# Power-Sheet-1.net
KiCad netlist of a schematic drawn in Altium Designer
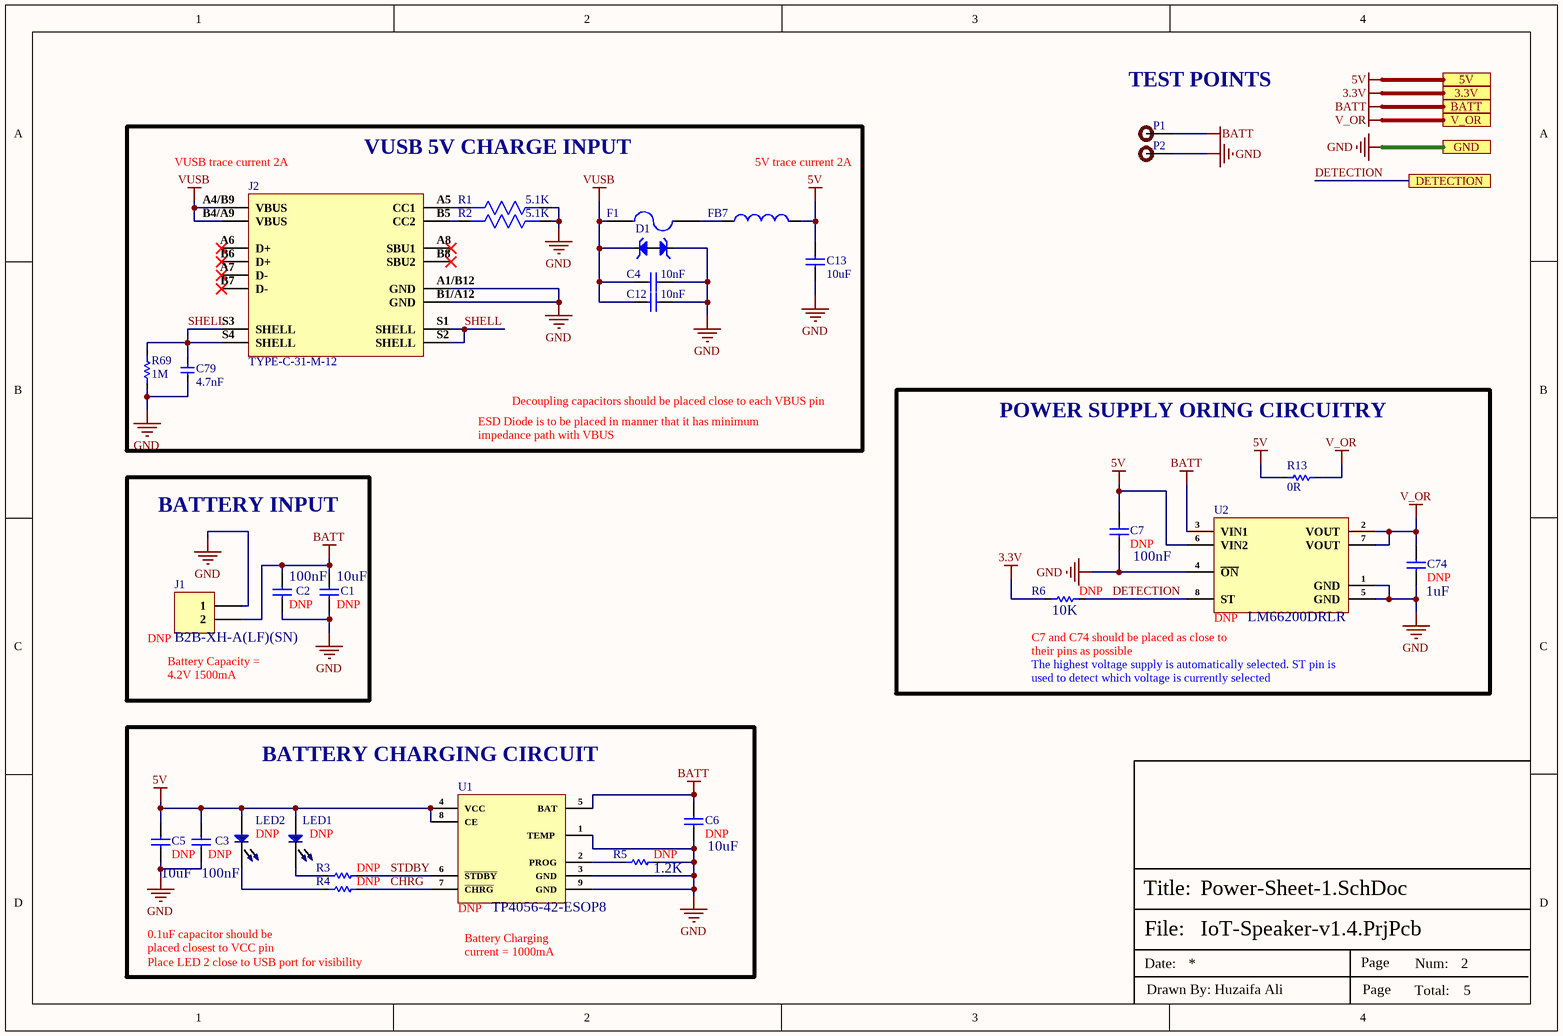
[diagram p0: Power-Sheet-1.SchDoc]

(export (version "E")
  (design (tool "Eeschema 10.0.6"))
  (components
    (comp (ref "C1")
      (value "DNP")
      (footprint "Cap-0805")
      (description "CAP CER 10UF 25V X5R 0805")
      (fields
        (field (name "MANUFACTURER") "Yageo")
        (field (name "MANUFACTURER PART NUMBER") "CC0805KKX5R8BB106")
      )
      (libsource (lib "eSpark_centralized_Library(2022)") (part "CC0805KKX5R8BB106"))
    )
    (comp (ref "C2")
      (value "DNP")
      (footprint "Cap-0402")
      (description "CAP CER 0.1UF 25V X5R 0402")
      (fields
        (field (name "MANUFACTURER") "Yageo")
        (field (name "MANUFACTURER PART NUMBER") "CC0402KRX5R8BB104")
      )
      (libsource (lib "eSpark_centralized_Library(2022)") (part "CC0402KRX5R8BB104"))
    )
    (comp (ref "C3")
      (value "DNP")
      (footprint "Cap-0402")
      (description "CAP CER 0.1UF 25V X5R 0402")
      (fields
        (field (name "MANUFACTURER") "Yageo")
        (field (name "MANUFACTURER PART NUMBER") "CC0402KRX5R8BB104")
      )
      (libsource (lib "eSpark_centralized_Library(2022)") (part "CC0402KRX5R8BB104"))
    )
    (comp (ref "C4")
      (value "10nF")
      (footprint "Cap-0603")
      (description "CAP CER 10000PF 50V C0G/NPO 0603")
      (fields
        (field (name "MANUFACTURER") "Yageo")
        (field (name "MANUFACTURER PART NUMBER") "CC0603JRNPO9BN103")
      )
      (libsource (lib "eSpark_centralized_Library(2022)") (part "CC0603JRNPO9BN103"))
    )
    (comp (ref "C5")
      (value "DNP")
      (footprint "Cap-0805")
      (description "CAP CER 10UF 25V X5R 0805")
      (fields
        (field (name "MANUFACTURER") "Yageo")
        (field (name "MANUFACTURER PART NUMBER") "CC0805KKX5R8BB106")
      )
      (libsource (lib "eSpark_centralized_Library(2022)") (part "CC0805KKX5R8BB106"))
    )
    (comp (ref "C6")
      (value "DNP")
      (footprint "Cap-0805")
      (description "CAP CER 10UF 25V X5R 0805")
      (fields
        (field (name "MANUFACTURER") "Yageo")
        (field (name "MANUFACTURER PART NUMBER") "CC0805KKX5R8BB106")
      )
      (libsource (lib "eSpark_centralized_Library(2022)") (part "CC0805KKX5R8BB106"))
    )
    (comp (ref "C7")
      (value "DNP")
      (footprint "Cap-0402")
      (description "CAP CER 0.1UF 25V X5R 0402")
      (fields
        (field (name "MANUFACTURER") "Yageo")
        (field (name "MANUFACTURER PART NUMBER") "CC0402KRX5R8BB104")
      )
      (libsource (lib "eSpark_centralized_Library(2022)") (part "CC0402KRX5R8BB104"))
    )
    (comp (ref "C12")
      (value "10nF")
      (footprint "Cap-0603")
      (description "CAP CER 10000PF 50V C0G/NPO 0603")
      (fields
        (field (name "MANUFACTURER") "Yageo")
        (field (name "MANUFACTURER PART NUMBER") "CC0603JRNPO9BN103")
      )
      (libsource (lib "eSpark_centralized_Library(2022)") (part "CC0603JRNPO9BN103"))
    )
    (comp (ref "C13")
      (value "10uF")
      (footprint "Cap-0805")
      (description "CAP CER 10UF 25V X5R 0805")
      (fields
        (field (name "MANUFACTURER") "Yageo")
        (field (name "MANUFACTURER PART NUMBER") "CC0805KKX5R8BB106")
      )
      (libsource (lib "eSpark_centralized_Library(2022)") (part "CC0805KKX5R8BB106"))
    )
    (comp (ref "C74")
      (value "DNP")
      (footprint "Cap-0603")
      (description "CAP CER 1UF 25V X5R 0603")
      (fields
        (field (name "MANUFACTURER") "Yageo")
        (field (name "MANUFACTURER PART NUMBER") "CC0603KRX5R8BB105")
      )
      (libsource (lib "eSpark_centralized_Library(2022)") (part "CC0603KRX5R8BB105"))
    )
    (comp (ref "C79")
      (value "4.7nF")
      (footprint "Cap-1206")
      (description "CAP CER 4700PF 1KV X7R 1206")
      (fields
        (field (name "MANUFACTURER") "Yageo")
        (field (name "MANUFACTURER PART NUMBER") "CC1206KKX7RCBB472")
      )
      (libsource (lib "eSpark Libraries") (part "CC1206KKX7RCBB472"))
    )
    (comp (ref "D1")
      (value "PESD5V0H1BSFYL")
      (footprint "DSN0603-2")
      (description "TVS DIODE 5VWM 6.3VC DSN0603-2")
      (fields (field (name "MANUFACTURER") "Nexperia") (field (name "LCSC PART NUMBER") "C477989"))
      (libsource (lib "eSpark Libraries") (part "PESD5V0H1BSFYL"))
    )
    (comp (ref "F1")
      (value "BSMD0805L-200")
      (footprint "Fuse-0805")
      (description "6V 2A 50A 1W -40℃~+85℃ 4A 4mΩ 5s 45mΩ 0805 Resettable Fuses ROHS")
      (fields (field (name "MANUFACTURER") "BHFUSE") (field (name "LCSC PART NUMBER") "C2757931"))
      (libsource (lib "eSpark_centralized_Library(2022)") (part "BSMD0805L-200"))
    )
    (comp (ref "FB7")
      (value "100MHz")
      (footprint "IND-1206")
      (description "FERRITE BEAD 120 OHM 1206 1LN")
      (fields
        (field (name "MANUFACTURER") "Murata")
        (field (name "MANUFACTURER PART NUMBER") "BLM31PG121SN1L")
      )
      (libsource (lib "eSpark_centralized_Library(2022)") (part "BLM31PG121SN1L"))
    )
    (comp (ref "J1")
      (value "DNP")
      (footprint "B2B-XH-A(LF)(SN)_")
      (description "Conn Shrouded Header (4 Sides) HDR 2 POS 2.5mm Solder ST Thru-Hole Box")
      (fields
        (field (name "MANUFACTURER") "JST")
        (field (name "MANUFACTURER PART NUMBER") "B2B-XH-A(LF)(SN)")
      )
      (libsource (lib "eSpark_centralized_Library(2022)") (part "B2B-XH-A(LF)(SN)"))
    )
    (comp (ref "J2")
      (value "TYPE-C-31-M-12")
      (footprint "TYPE-C-31-M-12_")
      (description "250mA 1 16 Female Type-C SMD USB Connectors ROHS")
      (fields
        (field (name "MANUFACTURER") "Korean Hroparts Elec")
        (field (name "LCSC PART NUMBER") "C165948")
      )
      (libsource (lib "eSpark_centralized_Library(2022)") (part "TYPE-C-31-M-12"))
    )
    (comp (ref "LED1")
      (value "DNP")
      (footprint "LED-0603")
      (description "Emerald 0603 Light Emitting Diodes (LED) ROHS")
      (fields
        (field (name "MANUFACTURER") "Foshan NationStar Optoelectronics")
        (field (name "MANUFACTURER PART NUMBER") "NCD0603G2")
      )
      (libsource (lib "eSpark_centralized_Library(2022)") (part "NCD0603G2"))
    )
    (comp (ref "LED2")
      (value "DNP")
      (footprint "LED-0603")
      (description "0603 Light Emitting Diodes (LED) ROHS")
      (fields
        (field (name "MANUFACTURER") "Foshan NationStar Optoelectronics")
        (field (name "MANUFACTURER PART NUMBER") "NCD0603R3")
      )
      (libsource (lib "eSpark_centralized_Library(2022)") (part "NCD0603R3"))
    )
    (comp (ref "P1")
      (value "TEST POINT")
      (footprint "Test-point")
      (description "Test Point ON")
      (libsource (lib "eSpark_centralized_Library(2022)") (part "TEST POINT"))
    )
    (comp (ref "P2")
      (value "TEST POINT")
      (footprint "Test-point")
      (description "Test Point ON")
      (libsource (lib "eSpark_centralized_Library(2022)") (part "TEST POINT"))
    )
    (comp (ref "R1")
      (value "5.1K")
      (footprint "Res-0603")
      (description "RES 5.1K OHM 1% 1/10W 0603")
      (fields
        (field (name "MANUFACTURER") "Yageo")
        (field (name "MANUFACTURER PART NUMBER") "RC0603FR-075K1L")
      )
      (libsource (lib "eSpark_centralized_Library(2022)") (part "RC0603FR-075K1L"))
    )
    (comp (ref "R2")
      (value "5.1K")
      (footprint "Res-0603")
      (description "RES 5.1K OHM 1% 1/10W 0603")
      (fields
        (field (name "MANUFACTURER") "Yageo")
        (field (name "MANUFACTURER PART NUMBER") "RC0603FR-075K1L")
      )
      (libsource (lib "eSpark_centralized_Library(2022)") (part "RC0603FR-075K1L"))
    )
    (comp (ref "R3")
      (value "DNP")
      (footprint "Res-0603")
      (description "RES SMD 220 OHM 1% 1/10W 0603")
      (fields
        (field (name "MANUFACTURER") "Yageo")
        (field (name "MANUFACTURER PART NUMBER") "RC0603FR-07220RL")
      )
      (libsource (lib "eSpark_centralized_Library(2022)") (part "RC0603FR-07220RL"))
    )
    (comp (ref "R4")
      (value "DNP")
      (footprint "Res-0603")
      (description "RES  SMD 330R 100 mW 0603")
      (fields
        (field (name "MANUFACTURER") "Yageo")
        (field (name "MANUFACTURER PART NUMBER") "RC0603JR-07330RL")
      )
      (libsource (lib "eSpark_centralized_Library(2022)") (part "RC0603JR-07330RL"))
    )
    (comp (ref "R5")
      (value "DNP")
      (footprint "Res-0603")
      (description "Thick Film Resistors 75V 1.2kΩ 0603 Chip Resistor - Surface Mount ROHS")
      (fields
        (field (name "MANUFACTURER") "UNI-ROYAL")
        (field (name "MANUFACTURER PART NUMBER") "0603WAF1201T5E")
      )
      (libsource (lib "eSpark_centralized_Library(2022)") (part "0603WAF1201T5E"))
    )
    (comp (ref "R6")
      (value "DNP")
      (footprint "Res-0603")
      (description "RES SMD 10K Ohm 1% 1/10W 0603")
      (fields
        (field (name "MANUFACTURER") "Yageo")
        (field (name "MANUFACTURER PART NUMBER") "RC0603FR-0710KL")
      )
      (libsource (lib "eSpark_centralized_Library(2022)") (part "RC0603FR-0710KL"))
    )
    (comp (ref "R13")
      (value "0R")
      (footprint "Res-0603")
      (description "RES 0 OHM JUMPER 1/10W 0603")
      (fields
        (field (name "MANUFACTURER") "Yageo")
        (field (name "MANUFACTURER PART NUMBER") "RC0603JR-070RL")
      )
      (libsource (lib "eSpark Libraries") (part "RC0603JR-070RL"))
    )
    (comp (ref "R69")
      (value "1M")
      (footprint "Res-0603")
      (description "RES SMD 1M OHM 1% 1/10W 0603")
      (fields
        (field (name "MANUFACTURER") "Yageo")
        (field (name "MANUFACTURER PART NUMBER") "RC0603FR-071ML")
      )
      (libsource (lib "eSpark Libraries") (part "RC0603FR-071ML"))
    )
    (comp (ref "U1")
      (value "DNP")
      (footprint "ESOP-8")
      (description "ESOP-8 Battery Management ICs ROHS")
      (fields
        (field (name "MANUFACTURER") "TOPPOWER")
        (field (name "MANUFACTURER PART NUMBER") "TP4056-42-ESOP8")
      )
      (libsource (lib "eSpark_centralized_Library(2022)") (part "TP4056-42-ESOP8"))
    )
    (comp (ref "U2")
      (value "DNP")
      (footprint "SOT-583")
      (description "OR Controller N+1 ORing Controller N-Channel 2:1 SOT-583")
      (fields
        (field (name "MANUFACTURER") "Texas Instruments")
        (field (name "MANUFACTURER PART NUMBER") "LM66200DRLR")
      )
      (libsource (lib "eSpark_centralized_Library(2022)") (part "LM66200DRLR"))
    )
  )
  (nets
    (net (code "1") (name "/CHRG") (class "Default")
      (node (ref "R4") (pin "2") (pinfunction "2_2") (pintype "passive"))
      (node (ref "U1") (pin "7") (pinfunction "~{CHRG}_7") (pintype "passive"))
    )
    (net (code "2") (name "/DETECTION") (class "Default")
      (node (ref "R6") (pin "2") (pinfunction "2_2") (pintype "passive"))
      (node (ref "U2") (pin "8") (pinfunction "ST_8") (pintype "passive"))
    )
    (net (code "3") (name "/SHELL") (class "Default")
      (node (ref "C79") (pin "2") (pinfunction "2_2") (pintype "passive"))
      (node (ref "J2") (pin "S1") (pinfunction "SHELL_S1") (pintype "passive"))
      (node (ref "J2") (pin "S2") (pinfunction "SHELL_S2") (pintype "passive"))
      (node (ref "J2") (pin "S3") (pinfunction "SHELL_S3") (pintype "passive"))
      (node (ref "J2") (pin "S4") (pinfunction "SHELL_S4") (pintype "passive"))
      (node (ref "R69") (pin "2") (pinfunction "2_2") (pintype "passive"))
    )
    (net (code "4") (name "/STDBY") (class "Default")
      (node (ref "R3") (pin "2") (pinfunction "2_2") (pintype "passive"))
      (node (ref "U1") (pin "6") (pinfunction "~{STDBY}_6") (pintype "passive"))
    )
    (net (code "5") (name "3.3V") (class "Default")
      (node (ref "R6") (pin "1") (pinfunction "1_1") (pintype "passive"))
    )
    (net (code "6") (name "5V") (class "Default")
      (node (ref "C13") (pin "2") (pinfunction "2_2") (pintype "passive"))
      (node (ref "C3") (pin "2") (pinfunction "2_2") (pintype "passive"))
      (node (ref "C5") (pin "2") (pinfunction "2_2") (pintype "passive"))
      (node (ref "C7") (pin "2") (pinfunction "2_2") (pintype "passive"))
      (node (ref "FB7") (pin "2") (pinfunction "2_2") (pintype "passive"))
      (node (ref "LED1") (pin "1") (pinfunction "1_1") (pintype "passive"))
      (node (ref "LED2") (pin "1") (pinfunction "1_1") (pintype "passive"))
      (node (ref "R13") (pin "1") (pinfunction "1_1") (pintype "passive"))
      (node (ref "U1") (pin "4") (pinfunction "VCC_4") (pintype "passive"))
      (node (ref "U1") (pin "8") (pinfunction "CE_8") (pintype "passive"))
      (node (ref "U2") (pin "6") (pinfunction "VIN2_6") (pintype "passive"))
    )
    (net (code "7") (name "BATT") (class "Default")
      (node (ref "C1") (pin "2") (pinfunction "2_2") (pintype "passive"))
      (node (ref "C2") (pin "2") (pinfunction "2_2") (pintype "passive"))
      (node (ref "C6") (pin "2") (pinfunction "2_2") (pintype "passive"))
      (node (ref "J1") (pin "2") (pinfunction "2_2") (pintype "passive"))
      (node (ref "P1") (pin "1") (pinfunction "1_1") (pintype "passive"))
      (node (ref "U1") (pin "5") (pinfunction "BAT_5") (pintype "passive"))
      (node (ref "U2") (pin "3") (pinfunction "VIN1_3") (pintype "passive"))
    )
    (net (code "8") (name "GND") (class "Default")
      (node (ref "C1") (pin "1") (pinfunction "1_1") (pintype "passive"))
      (node (ref "C12") (pin "2") (pinfunction "2_2") (pintype "passive"))
      (node (ref "C13") (pin "1") (pinfunction "1_1") (pintype "passive"))
      (node (ref "C2") (pin "1") (pinfunction "1_1") (pintype "passive"))
      (node (ref "C3") (pin "1") (pinfunction "1_1") (pintype "passive"))
      (node (ref "C4") (pin "2") (pinfunction "2_2") (pintype "passive"))
      (node (ref "C5") (pin "1") (pinfunction "1_1") (pintype "passive"))
      (node (ref "C6") (pin "1") (pinfunction "1_1") (pintype "passive"))
      (node (ref "C7") (pin "1") (pinfunction "1_1") (pintype "passive"))
      (node (ref "C74") (pin "1") (pinfunction "1_1") (pintype "passive"))
      (node (ref "C79") (pin "1") (pinfunction "1_1") (pintype "passive"))
      (node (ref "D1") (pin "2") (pinfunction "2_2") (pintype "passive"))
      (node (ref "J1") (pin "1") (pinfunction "1_1") (pintype "passive"))
      (node (ref "J2") (pin "A1/B12") (pinfunction "GND_A1/B12") (pintype "power_in"))
      (node (ref "J2") (pin "B1/A12") (pinfunction "GND_B1/A12") (pintype "power_in"))
      (node (ref "P2") (pin "1") (pinfunction "1_1") (pintype "passive"))
      (node (ref "R1") (pin "1") (pintype "passive"))
      (node (ref "R2") (pin "1") (pintype "passive"))
      (node (ref "R5") (pin "1") (pinfunction "1_1") (pintype "passive"))
      (node (ref "R69") (pin "1") (pinfunction "1_1") (pintype "passive"))
      (node (ref "U1") (pin "1") (pinfunction "TEMP_1") (pintype "passive"))
      (node (ref "U1") (pin "3") (pinfunction "GND_3") (pintype "passive"))
      (node (ref "U1") (pin "9") (pinfunction "GND_9") (pintype "passive"))
      (node (ref "U2") (pin "1") (pinfunction "GND_1") (pintype "passive"))
      (node (ref "U2") (pin "4") (pinfunction "~{ON}_4") (pintype "passive"))
      (node (ref "U2") (pin "5") (pinfunction "GND_5") (pintype "passive"))
    )
    (net (code "9") (name "Net-(F1-Pad2)") (class "Default")
      (node (ref "F1") (pin "2") (pinfunction "2_2") (pintype "passive"))
      (node (ref "FB7") (pin "1") (pinfunction "1_1") (pintype "passive"))
    )
    (net (code "10") (name "Net-(J2-CC1)") (class "Default")
      (node (ref "J2") (pin "A5") (pinfunction "CC1_A5") (pintype "passive"))
      (node (ref "R1") (pin "2") (pintype "passive"))
    )
    (net (code "11") (name "Net-(J2-CC2)") (class "Default")
      (node (ref "J2") (pin "B5") (pinfunction "CC2_B5") (pintype "passive"))
      (node (ref "R2") (pin "2") (pintype "passive"))
    )
    (net (code "12") (name "Net-(LED1-Pad2)") (class "Default")
      (node (ref "LED1") (pin "2") (pinfunction "2_2") (pintype "passive"))
      (node (ref "R3") (pin "1") (pinfunction "1_1") (pintype "passive"))
    )
    (net (code "13") (name "Net-(LED2-Pad2)") (class "Default")
      (node (ref "LED2") (pin "2") (pinfunction "2_2") (pintype "passive"))
      (node (ref "R4") (pin "1") (pinfunction "1_1") (pintype "passive"))
    )
    (net (code "14") (name "Net-(U1-PROG)") (class "Default")
      (node (ref "R5") (pin "2") (pinfunction "2_2") (pintype "passive"))
      (node (ref "U1") (pin "2") (pinfunction "PROG_2") (pintype "passive"))
    )
    (net (code "15") (name "VUSB") (class "Default")
      (node (ref "C12") (pin "1") (pinfunction "1_1") (pintype "passive"))
      (node (ref "C4") (pin "1") (pinfunction "1_1") (pintype "passive"))
      (node (ref "D1") (pin "1") (pinfunction "1_1") (pintype "passive"))
      (node (ref "F1") (pin "1") (pinfunction "1_1") (pintype "passive"))
      (node (ref "J2") (pin "A4/B9") (pinfunction "VBUS_A4/B9") (pintype "power_in"))
      (node (ref "J2") (pin "B4/A9") (pinfunction "VBUS_B4/A9") (pintype "power_in"))
    )
    (net (code "16") (name "V_OR") (class "Default")
      (node (ref "C74") (pin "2") (pinfunction "2_2") (pintype "passive"))
      (node (ref "R13") (pin "2") (pinfunction "2_2") (pintype "passive"))
      (node (ref "U2") (pin "2") (pinfunction "VOUT_2") (pintype "passive"))
      (node (ref "U2") (pin "7") (pinfunction "VOUT_7") (pintype "passive"))
    )
    (net (code "17") (name "unconnected-(J2-D+-PadA6)") (class "Default")
      (node (ref "J2") (pin "A6") (pinfunction "D+_A6") (pintype "passive+no_connect"))
    )
    (net (code "18") (name "unconnected-(J2-D+-PadB6)") (class "Default")
      (node (ref "J2") (pin "B6") (pinfunction "D+_B6") (pintype "passive+no_connect"))
    )
    (net (code "19") (name "unconnected-(J2-D--PadA7)") (class "Default")
      (node (ref "J2") (pin "A7") (pinfunction "D-_A7") (pintype "passive+no_connect"))
    )
    (net (code "20") (name "unconnected-(J2-D--PadB7)") (class "Default")
      (node (ref "J2") (pin "B7") (pinfunction "D-_B7") (pintype "passive+no_connect"))
    )
    (net (code "21") (name "unconnected-(J2-SBU1-PadA8)") (class "Default")
      (node (ref "J2") (pin "A8") (pinfunction "SBU1_A8") (pintype "passive+no_connect"))
    )
    (net (code "22") (name "unconnected-(J2-SBU2-PadB8)") (class "Default")
      (node (ref "J2") (pin "B8") (pinfunction "SBU2_B8") (pintype "passive+no_connect"))
    )
  )
)
